# Connectors.net
KiCad netlist of a schematic drawn in Altium Designer
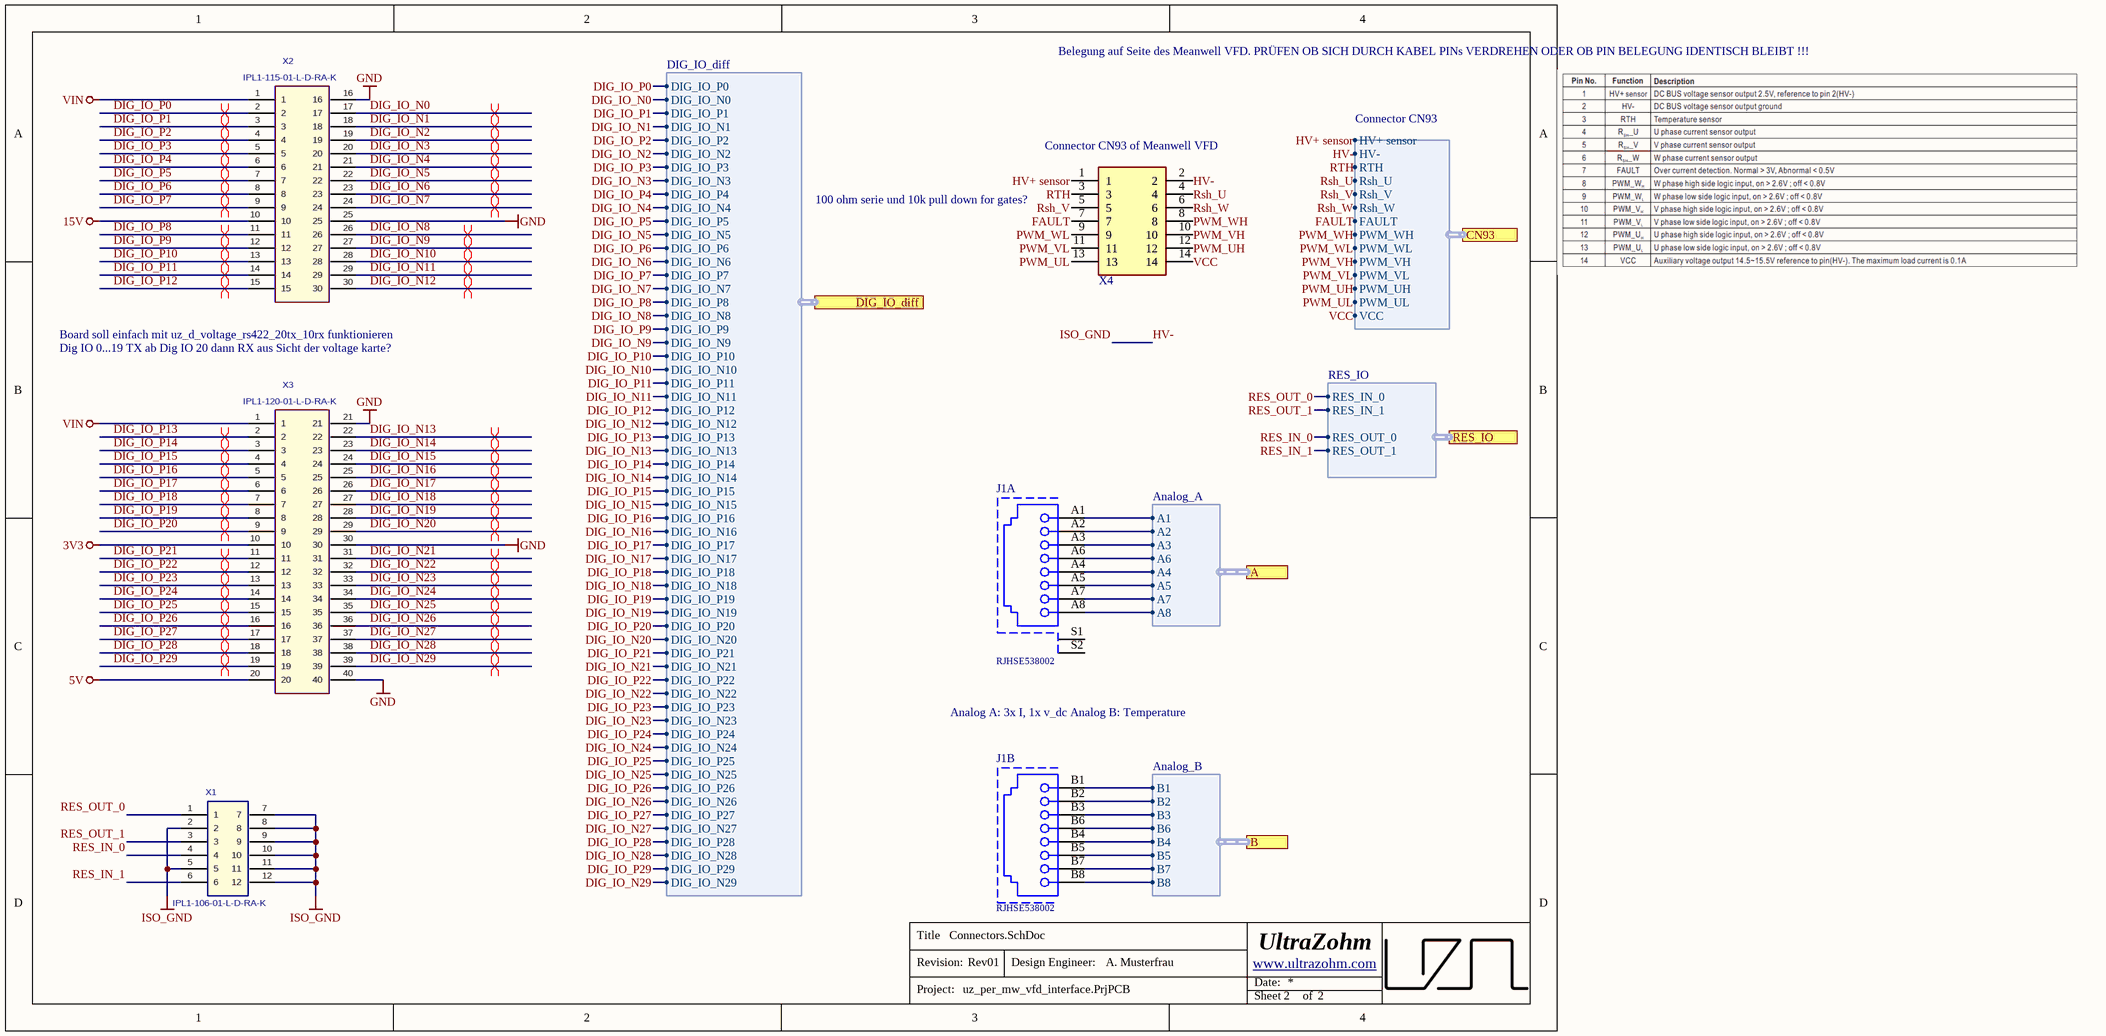
[diagram p0: Connectors.SchDoc]

(export (version "E")
  (design (tool "Eeschema 10.0.6"))
  (components
    (comp (ref "J1")
      (value "RJHSE538002")
      (footprint "RJHSE-5380-02")
      (description "CAT5, RJ45 Connector, 1x2")
      (fields (field (name "MANUFACTURER") "Amphenol") (field (name "CREATED FROM") "MGremer"))
      (libsource (lib "user") (part "RJHSE-5380-02"))
    )
    (comp (ref "X1")
      (value "IPL1-106-01-L-D-RA-K")
      (footprint "IPL1-106-01-L-D-RA-K")
      (description "2.54 mm Double Row Terminal Assembly (right angle)")
      (fields (field (name "MANUFACTURER") "SAMTEC") (field (name "CREATED FROM") "MGremer"))
      (libsource (lib "user") (part "IPL1-106-XX-X-D-X"))
    )
    (comp (ref "X2")
      (value "IPL1-115-01-L-D-RA-K")
      (footprint "IPL1-115-01-XX-D-RA")
      (description "Terminal Assembly, Double Row, Right Angle, Thru-Hole, 2.54 mm x 2.54 mm Pitch, 30 Pins")
      (fields (field (name "MANUFACTURER") "SAMTEC") (field (name "CREATED FROM") "TWendt"))
      (libsource (lib "user") (part "IPL1-115-01-XX-D-RA"))
    )
    (comp (ref "X3")
      (value "IPL1-120-01-L-D-RA-K")
      (footprint "IPL1-120-01-XX-D-RA")
      (description "Terminal Assembly, Double Row, Right Angle, Thru-Hole, 2.54 mm x 2.54 mm Pitch, 40 Pins")
      (fields (field (name "MANUFACTURER") "SAMTEC") (field (name "CREATED FROM") "TWendt"))
      (libsource (lib "user") (part "IPL1-120-01-XX-D-RA"))
    )
    (comp (ref "X4")
      (value "~")
      (footprint "DF11-14DP-2DS(24)")
      (description "Sockel & Kabelgehäuse 2MM R/A PCB HEADER 14P DR THRU-HOLE TIN")
      (fields
        (field (name "MANUFACTURER PART NUMBER") "DF11-14DP-2DS(24)")
        (field (name "MANUFACTURER") "Hirose Connector")
        (field (name "CREATED FROM") "FRosner")
      )
      (libsource (lib "user") (part "DF11-14DP-2DS(24)"))
    )
  )
  (nets
    (net (code "7") (name "/A1") (class "Default")
      (node (ref "J1") (pin "A1") (pinfunction "A1_A1") (pintype "passive"))
    )
    (net (code "8") (name "/A2") (class "Default")
      (node (ref "J1") (pin "A2") (pinfunction "A2_A2") (pintype "passive"))
    )
    (net (code "9") (name "/A3") (class "Default")
      (node (ref "J1") (pin "A3") (pinfunction "A3_A3") (pintype "passive"))
    )
    (net (code "10") (name "/A4") (class "Default")
      (node (ref "J1") (pin "A4") (pinfunction "A4_A4") (pintype "passive"))
    )
    (net (code "11") (name "/A5") (class "Default")
      (node (ref "J1") (pin "A5") (pinfunction "A5_A5") (pintype "passive"))
    )
    (net (code "12") (name "/A6") (class "Default")
      (node (ref "J1") (pin "A6") (pinfunction "A6_A6") (pintype "passive"))
    )
    (net (code "13") (name "/A7") (class "Default")
      (node (ref "J1") (pin "A7") (pinfunction "A7_A7") (pintype "passive"))
    )
    (net (code "14") (name "/A8") (class "Default")
      (node (ref "J1") (pin "A8") (pinfunction "A8_A8") (pintype "passive"))
    )
    (net (code "15") (name "/B1") (class "Default")
      (node (ref "J1") (pin "B1") (pinfunction "B1_B1") (pintype "passive"))
    )
    (net (code "16") (name "/B2") (class "Default")
      (node (ref "J1") (pin "B2") (pinfunction "B2_B2") (pintype "passive"))
    )
    (net (code "17") (name "/B3") (class "Default")
      (node (ref "J1") (pin "B3") (pinfunction "B3_B3") (pintype "passive"))
    )
    (net (code "18") (name "/B4") (class "Default")
      (node (ref "J1") (pin "B4") (pinfunction "B4_B4") (pintype "passive"))
    )
    (net (code "19") (name "/B5") (class "Default")
      (node (ref "J1") (pin "B5") (pinfunction "B5_B5") (pintype "passive"))
    )
    (net (code "20") (name "/B6") (class "Default")
      (node (ref "J1") (pin "B6") (pinfunction "B6_B6") (pintype "passive"))
    )
    (net (code "21") (name "/B7") (class "Default")
      (node (ref "J1") (pin "B7") (pinfunction "B7_B7") (pintype "passive"))
    )
    (net (code "22") (name "/B8") (class "Default")
      (node (ref "J1") (pin "B8") (pinfunction "B8_B8") (pintype "passive"))
    )
    (net (code "23") (name "/DIG_IO_N0") (class "Default")
      (node (ref "X2") (pin "17") (pinfunction "17_17") (pintype "passive"))
    )
    (net (code "24") (name "/DIG_IO_N1") (class "Default")
      (node (ref "X2") (pin "18") (pinfunction "18_18") (pintype "passive"))
    )
    (net (code "25") (name "/DIG_IO_N2") (class "Default")
      (node (ref "X2") (pin "19") (pinfunction "19_19") (pintype "passive"))
    )
    (net (code "26") (name "/DIG_IO_N3") (class "Default")
      (node (ref "X2") (pin "20") (pinfunction "20_20") (pintype "passive"))
    )
    (net (code "27") (name "/DIG_IO_N4") (class "Default")
      (node (ref "X2") (pin "21") (pinfunction "21_21") (pintype "passive"))
    )
    (net (code "28") (name "/DIG_IO_N5") (class "Default")
      (node (ref "X2") (pin "22") (pinfunction "22_22") (pintype "passive"))
    )
    (net (code "29") (name "/DIG_IO_N6") (class "Default")
      (node (ref "X2") (pin "23") (pinfunction "23_23") (pintype "passive"))
    )
    (net (code "30") (name "/DIG_IO_N7") (class "Default")
      (node (ref "X2") (pin "24") (pinfunction "24_24") (pintype "passive"))
    )
    (net (code "31") (name "/DIG_IO_N8") (class "Default")
      (node (ref "X2") (pin "26") (pinfunction "26_26") (pintype "passive"))
    )
    (net (code "32") (name "/DIG_IO_N9") (class "Default")
      (node (ref "X2") (pin "27") (pinfunction "27_27") (pintype "passive"))
    )
    (net (code "33") (name "/DIG_IO_N10") (class "Default")
      (node (ref "X2") (pin "28") (pinfunction "28_28") (pintype "passive"))
    )
    (net (code "34") (name "/DIG_IO_N11") (class "Default")
      (node (ref "X2") (pin "29") (pinfunction "29_29") (pintype "passive"))
    )
    (net (code "35") (name "/DIG_IO_N12") (class "Default")
      (node (ref "X2") (pin "30") (pinfunction "30_30") (pintype "passive"))
    )
    (net (code "36") (name "/DIG_IO_N13") (class "Default")
      (node (ref "X3") (pin "22") (pinfunction "22_22") (pintype "passive"))
    )
    (net (code "37") (name "/DIG_IO_N14") (class "Default")
      (node (ref "X3") (pin "23") (pinfunction "23_23") (pintype "passive"))
    )
    (net (code "38") (name "/DIG_IO_N15") (class "Default")
      (node (ref "X3") (pin "24") (pinfunction "24_24") (pintype "passive"))
    )
    (net (code "39") (name "/DIG_IO_N16") (class "Default")
      (node (ref "X3") (pin "25") (pinfunction "25_25") (pintype "passive"))
    )
    (net (code "40") (name "/DIG_IO_N17") (class "Default")
      (node (ref "X3") (pin "26") (pinfunction "26_26") (pintype "passive"))
    )
    (net (code "41") (name "/DIG_IO_N18") (class "Default")
      (node (ref "X3") (pin "27") (pinfunction "27_27") (pintype "passive"))
    )
    (net (code "42") (name "/DIG_IO_N19") (class "Default")
      (node (ref "X3") (pin "28") (pinfunction "28_28") (pintype "passive"))
    )
    (net (code "43") (name "/DIG_IO_N20") (class "Default")
      (node (ref "X3") (pin "29") (pinfunction "29_29") (pintype "passive"))
    )
    (net (code "44") (name "/DIG_IO_N21") (class "Default")
      (node (ref "X3") (pin "31") (pinfunction "31_31") (pintype "passive"))
    )
    (net (code "45") (name "/DIG_IO_N22") (class "Default")
      (node (ref "X3") (pin "32") (pinfunction "32_32") (pintype "passive"))
    )
    (net (code "46") (name "/DIG_IO_N23") (class "Default")
      (node (ref "X3") (pin "33") (pinfunction "33_33") (pintype "passive"))
    )
    (net (code "47") (name "/DIG_IO_N24") (class "Default")
      (node (ref "X3") (pin "34") (pinfunction "34_34") (pintype "passive"))
    )
    (net (code "48") (name "/DIG_IO_N25") (class "Default")
      (node (ref "X3") (pin "35") (pinfunction "35_35") (pintype "passive"))
    )
    (net (code "49") (name "/DIG_IO_N26") (class "Default")
      (node (ref "X3") (pin "36") (pinfunction "36_36") (pintype "passive"))
    )
    (net (code "50") (name "/DIG_IO_N27") (class "Default")
      (node (ref "X3") (pin "37") (pinfunction "37_37") (pintype "passive"))
    )
    (net (code "51") (name "/DIG_IO_N28") (class "Default")
      (node (ref "X3") (pin "38") (pinfunction "38_38") (pintype "passive"))
    )
    (net (code "52") (name "/DIG_IO_N29") (class "Default")
      (node (ref "X3") (pin "39") (pinfunction "39_39") (pintype "passive"))
    )
    (net (code "53") (name "/DIG_IO_P0") (class "Default")
      (node (ref "X2") (pin "2") (pinfunction "2_2") (pintype "passive"))
    )
    (net (code "54") (name "/DIG_IO_P1") (class "Default")
      (node (ref "X2") (pin "3") (pinfunction "3_3") (pintype "passive"))
    )
    (net (code "55") (name "/DIG_IO_P2") (class "Default")
      (node (ref "X2") (pin "4") (pinfunction "4_4") (pintype "passive"))
    )
    (net (code "56") (name "/DIG_IO_P3") (class "Default")
      (node (ref "X2") (pin "5") (pinfunction "5_5") (pintype "passive"))
    )
    (net (code "57") (name "/DIG_IO_P4") (class "Default")
      (node (ref "X2") (pin "6") (pinfunction "6_6") (pintype "passive"))
    )
    (net (code "58") (name "/DIG_IO_P5") (class "Default")
      (node (ref "X2") (pin "7") (pinfunction "7_7") (pintype "passive"))
    )
    (net (code "59") (name "/DIG_IO_P6") (class "Default")
      (node (ref "X2") (pin "8") (pinfunction "8_8") (pintype "passive"))
    )
    (net (code "60") (name "/DIG_IO_P7") (class "Default")
      (node (ref "X2") (pin "9") (pinfunction "9_9") (pintype "passive"))
    )
    (net (code "61") (name "/DIG_IO_P8") (class "Default")
      (node (ref "X2") (pin "11") (pinfunction "11_11") (pintype "passive"))
    )
    (net (code "62") (name "/DIG_IO_P9") (class "Default")
      (node (ref "X2") (pin "12") (pinfunction "12_12") (pintype "passive"))
    )
    (net (code "63") (name "/DIG_IO_P10") (class "Default")
      (node (ref "X2") (pin "13") (pinfunction "13_13") (pintype "passive"))
    )
    (net (code "64") (name "/DIG_IO_P11") (class "Default")
      (node (ref "X2") (pin "14") (pinfunction "14_14") (pintype "passive"))
    )
    (net (code "65") (name "/DIG_IO_P12") (class "Default")
      (node (ref "X2") (pin "15") (pinfunction "15_15") (pintype "passive"))
    )
    (net (code "66") (name "/DIG_IO_P13") (class "Default")
      (node (ref "X3") (pin "2") (pinfunction "2_2") (pintype "passive"))
    )
    (net (code "67") (name "/DIG_IO_P14") (class "Default")
      (node (ref "X3") (pin "3") (pinfunction "3_3") (pintype "passive"))
    )
    (net (code "68") (name "/DIG_IO_P15") (class "Default")
      (node (ref "X3") (pin "4") (pinfunction "4_4") (pintype "passive"))
    )
    (net (code "69") (name "/DIG_IO_P16") (class "Default")
      (node (ref "X3") (pin "5") (pinfunction "5_5") (pintype "passive"))
    )
    (net (code "70") (name "/DIG_IO_P17") (class "Default")
      (node (ref "X3") (pin "6") (pinfunction "6_6") (pintype "passive"))
    )
    (net (code "71") (name "/DIG_IO_P18") (class "Default")
      (node (ref "X3") (pin "7") (pinfunction "7_7") (pintype "passive"))
    )
    (net (code "72") (name "/DIG_IO_P19") (class "Default")
      (node (ref "X3") (pin "8") (pinfunction "8_8") (pintype "passive"))
    )
    (net (code "73") (name "/DIG_IO_P20") (class "Default")
      (node (ref "X3") (pin "9") (pinfunction "9_9") (pintype "passive"))
    )
    (net (code "74") (name "/DIG_IO_P21") (class "Default")
      (node (ref "X3") (pin "11") (pinfunction "11_11") (pintype "passive"))
    )
    (net (code "75") (name "/DIG_IO_P22") (class "Default")
      (node (ref "X3") (pin "12") (pinfunction "12_12") (pintype "passive"))
    )
    (net (code "76") (name "/DIG_IO_P23") (class "Default")
      (node (ref "X3") (pin "13") (pinfunction "13_13") (pintype "passive"))
    )
    (net (code "77") (name "/DIG_IO_P24") (class "Default")
      (node (ref "X3") (pin "14") (pinfunction "14_14") (pintype "passive"))
    )
    (net (code "78") (name "/DIG_IO_P25") (class "Default")
      (node (ref "X3") (pin "15") (pinfunction "15_15") (pintype "passive"))
    )
    (net (code "79") (name "/DIG_IO_P26") (class "Default")
      (node (ref "X3") (pin "16") (pinfunction "16_16") (pintype "passive"))
    )
    (net (code "80") (name "/DIG_IO_P27") (class "Default")
      (node (ref "X3") (pin "17") (pinfunction "17_17") (pintype "passive"))
    )
    (net (code "81") (name "/DIG_IO_P28") (class "Default")
      (node (ref "X3") (pin "18") (pinfunction "18_18") (pintype "passive"))
    )
    (net (code "82") (name "/DIG_IO_P29") (class "Default")
      (node (ref "X3") (pin "19") (pinfunction "19_19") (pintype "passive"))
    )
    (net (code "83") (name "/FAULT") (class "Default")
      (node (ref "X4") (pin "7") (pinfunction "7_7") (pintype "passive"))
    )
    (net (code "84") (name "/HV+ sensor") (class "Default")
      (node (ref "X4") (pin "1") (pinfunction "1_1") (pintype "passive"))
    )
    (net (code "85") (name "/PWM_UH") (class "Default")
      (node (ref "X4") (pin "12") (pinfunction "12_12") (pintype "passive"))
    )
    (net (code "86") (name "/PWM_UL") (class "Default")
      (node (ref "X4") (pin "13") (pinfunction "13_13") (pintype "passive"))
    )
    (net (code "87") (name "/PWM_VH") (class "Default")
      (node (ref "X4") (pin "10") (pinfunction "10_10") (pintype "passive"))
    )
    (net (code "88") (name "/PWM_VL") (class "Default")
      (node (ref "X4") (pin "11") (pinfunction "11_11") (pintype "passive"))
    )
    (net (code "89") (name "/PWM_WH") (class "Default")
      (node (ref "X4") (pin "8") (pinfunction "8_8") (pintype "passive"))
    )
    (net (code "90") (name "/PWM_WL") (class "Default")
      (node (ref "X4") (pin "9") (pinfunction "9_9") (pintype "passive"))
    )
    (net (code "91") (name "/RES_IN_0") (class "Default")
      (node (ref "X1") (pin "4") (pinfunction "4_4") (pintype "passive"))
    )
    (net (code "92") (name "/RES_IN_1") (class "Default")
      (node (ref "X1") (pin "6") (pinfunction "6_6") (pintype "passive"))
    )
    (net (code "93") (name "/RES_OUT_0") (class "Default")
      (node (ref "X1") (pin "1") (pinfunction "1_1") (pintype "passive"))
    )
    (net (code "94") (name "/RES_OUT_1") (class "Default")
      (node (ref "X1") (pin "3") (pinfunction "3_3") (pintype "passive"))
    )
    (net (code "95") (name "/RTH") (class "Default")
      (node (ref "X4") (pin "3") (pinfunction "3_3") (pintype "passive"))
    )
    (net (code "96") (name "/Rsh_U") (class "Default")
      (node (ref "X4") (pin "4") (pinfunction "4_4") (pintype "passive"))
    )
    (net (code "97") (name "/Rsh_V") (class "Default")
      (node (ref "X4") (pin "5") (pinfunction "5_5") (pintype "passive"))
    )
    (net (code "98") (name "/Rsh_W") (class "Default")
      (node (ref "X4") (pin "6") (pinfunction "6_6") (pintype "passive"))
    )
    (net (code "99") (name "/VCC") (class "Default")
      (node (ref "X4") (pin "14") (pinfunction "14_14") (pintype "passive"))
    )
    (net (code "105") (name "3V3") (class "Default")
      (node (ref "X3") (pin "10") (pinfunction "10_10") (pintype "passive"))
    )
    (net (code "106") (name "5V") (class "Default")
      (node (ref "X3") (pin "20") (pinfunction "20_20") (pintype "passive"))
    )
    (net (code "107") (name "15V") (class "Default")
      (node (ref "X2") (pin "10") (pinfunction "10_10") (pintype "passive"))
    )
    (net (code "108") (name "GND") (class "Default")
      (node (ref "X2") (pin "16") (pinfunction "16_16") (pintype "passive"))
      (node (ref "X2") (pin "25") (pinfunction "25_25") (pintype "passive"))
      (node (ref "X3") (pin "21") (pinfunction "21_21") (pintype "passive"))
      (node (ref "X3") (pin "30") (pinfunction "30_30") (pintype "passive"))
      (node (ref "X3") (pin "40") (pinfunction "40_40") (pintype "passive"))
    )
    (net (code "109") (name "ISO_GND") (class "Default")
      (node (ref "X1") (pin "10") (pinfunction "10_10") (pintype "passive"))
      (node (ref "X1") (pin "11") (pinfunction "11_11") (pintype "passive"))
      (node (ref "X1") (pin "12") (pinfunction "12_12") (pintype "passive"))
      (node (ref "X1") (pin "2") (pinfunction "2_2") (pintype "passive"))
      (node (ref "X1") (pin "5") (pinfunction "5_5") (pintype "passive"))
      (node (ref "X1") (pin "7") (pinfunction "7_7") (pintype "passive"))
      (node (ref "X1") (pin "8") (pinfunction "8_8") (pintype "passive"))
      (node (ref "X1") (pin "9") (pinfunction "9_9") (pintype "passive"))
      (node (ref "X4") (pin "2") (pinfunction "2_2") (pintype "passive"))
    )
    (net (code "110") (name "VIN") (class "Default")
      (node (ref "X2") (pin "1") (pinfunction "1_1") (pintype "passive"))
      (node (ref "X3") (pin "1") (pinfunction "1_1") (pintype "passive"))
    )
    (net (code "111") (name "unconnected-(J1-PadS1)") (class "Default")
      (node (ref "J1") (pin "S1") (pinfunction "S1_S1") (pintype "passive"))
    )
    (net (code "112") (name "unconnected-(J1-PadS2)") (class "Default")
      (node (ref "J1") (pin "S2") (pinfunction "S2_S2") (pintype "passive"))
    )
  )
)
